# RFID_Reader.net
KiCad netlist of a schematic drawn in Altium Designer
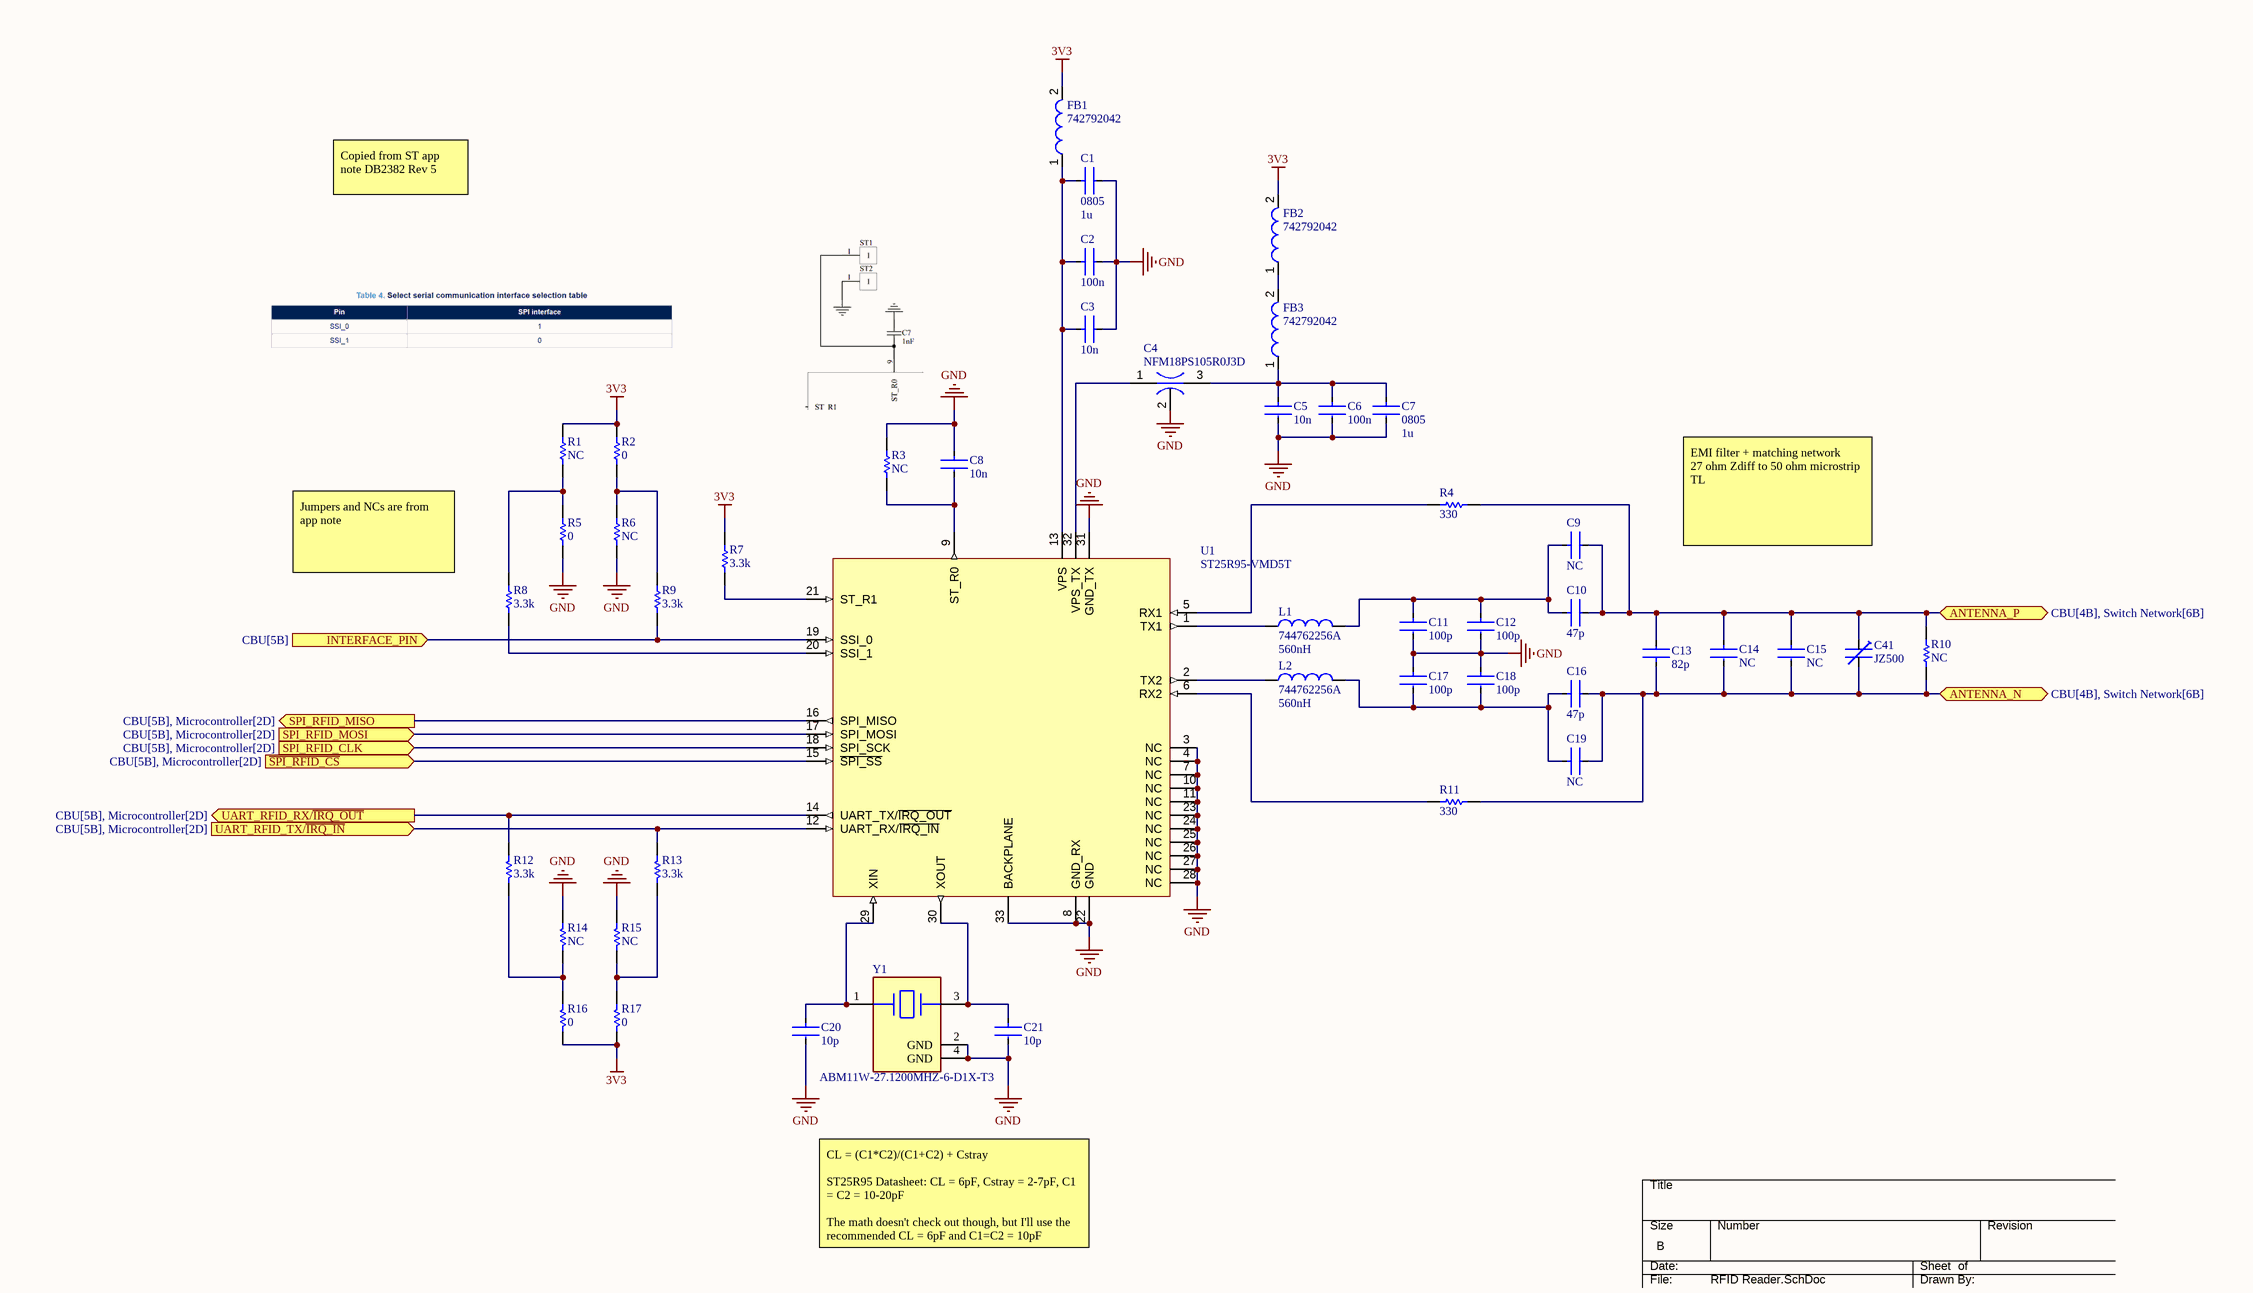
[diagram p0: RFID Reader.SchDoc]

(export (version "E")
  (design (tool "Eeschema 10.0.6"))
  (components
    (comp (ref "C1")
      (value "1u")
      (footprint "FP-0805-Capacitor-CL21-IPC_B")
      (description "CAP CER 50V X7R 0805")
      (fields
        (field (name "TOLERANCE") "0.1")
        (field (name "MANUFACTURER") "KEMET")
        (field (name "PACKAGE") "0805")
      )
      (libsource (lib "CBU-PCB") (part "Ceramic Capacitor 0805"))
    )
    (comp (ref "C2")
      (value "100n")
      (footprint "FP-0603-Capacitor-CL10-IPC_B")
      (description "CAP CER 50V X7R 0603")
      (fields (field (name "TOLERANCE") "0.1") (field (name "MANUFACTURER") "KEMET"))
      (libsource (lib "CBU-PCB") (part "Ceramic Capacitor 0603"))
    )
    (comp (ref "C3")
      (value "10n")
      (footprint "FP-0603-Capacitor-CL10-IPC_B")
      (description "CAP CER 50V X7R 0603")
      (fields (field (name "TOLERANCE") "0.1") (field (name "MANUFACTURER") "KEMET"))
      (libsource (lib "CBU-PCB") (part "Ceramic Capacitor 0603"))
    )
    (comp (ref "C4")
      (value "NFM18PS105R0J3D")
      (footprint "FP-NFM18-0_1-e0_05_0_35-MFG")
      (fields (field (name "VOLTAGE") "6.3V") (field (name "TOLERANCE") "20%"))
      (libsource (lib "CBU-PCB") (part "NFM18PS105R0J3D"))
    )
    (comp (ref "C5")
      (value "10n")
      (footprint "FP-0603-Capacitor-CL10-IPC_B")
      (description "CAP CER 50V X7R 0603")
      (fields (field (name "TOLERANCE") "0.1") (field (name "MANUFACTURER") "KEMET"))
      (libsource (lib "CBU-PCB") (part "Ceramic Capacitor 0603"))
    )
    (comp (ref "C6")
      (value "100n")
      (footprint "FP-0603-Capacitor-CL10-IPC_B")
      (description "CAP CER 50V X7R 0603")
      (fields (field (name "TOLERANCE") "0.1") (field (name "MANUFACTURER") "KEMET"))
      (libsource (lib "CBU-PCB") (part "Ceramic Capacitor 0603"))
    )
    (comp (ref "C7")
      (value "1u")
      (footprint "FP-0805-Capacitor-CL21-IPC_B")
      (description "CAP CER 50V X7R 0805")
      (fields
        (field (name "TOLERANCE") "0.1")
        (field (name "MANUFACTURER") "KEMET")
        (field (name "PACKAGE") "0805")
      )
      (libsource (lib "CBU-PCB") (part "Ceramic Capacitor 0805"))
    )
    (comp (ref "C8")
      (value "10n")
      (footprint "FP-0603-Capacitor-CL10-IPC_B")
      (description "CAP CER 50V X7R 0603")
      (fields (field (name "TOLERANCE") "0.1") (field (name "MANUFACTURER") "KEMET"))
      (libsource (lib "CBU-PCB") (part "Ceramic Capacitor 0603"))
    )
    (comp (ref "C9")
      (value "NC")
      (footprint "FP-0603-Capacitor-CL10-IPC_B")
      (description "CAP CER 50V X7R 0603")
      (fields (field (name "TOLERANCE") "0.1") (field (name "MANUFACTURER") "KEMET"))
      (libsource (lib "CBU-PCB") (part "Ceramic Capacitor 0603"))
    )
    (comp (ref "C10")
      (value "47p")
      (footprint "FP-0603-Capacitor-CL10-IPC_B")
      (description "CAP CER 50V X7R 0603")
      (fields (field (name "TOLERANCE") "0.1") (field (name "MANUFACTURER") "KEMET"))
      (libsource (lib "CBU-PCB") (part "Ceramic Capacitor 0603"))
    )
    (comp (ref "C11")
      (value "100p")
      (footprint "FP-0603-Capacitor-CL10-IPC_B")
      (description "CAP CER 50V X7R 0603")
      (fields (field (name "TOLERANCE") "0.1") (field (name "MANUFACTURER") "KEMET"))
      (libsource (lib "CBU-PCB") (part "Ceramic Capacitor 0603"))
    )
    (comp (ref "C12")
      (value "100p")
      (footprint "FP-0603-Capacitor-CL10-IPC_B")
      (description "CAP CER 50V X7R 0603")
      (fields (field (name "TOLERANCE") "0.1") (field (name "MANUFACTURER") "KEMET"))
      (libsource (lib "CBU-PCB") (part "Ceramic Capacitor 0603"))
    )
    (comp (ref "C13")
      (value "82p")
      (footprint "FP-0603-Capacitor-CL10-IPC_B")
      (description "CAP CER 50V X7R 0603")
      (fields (field (name "TOLERANCE") "0.1") (field (name "MANUFACTURER") "KEMET"))
      (libsource (lib "CBU-PCB") (part "Ceramic Capacitor 0603"))
    )
    (comp (ref "C14")
      (value "NC")
      (footprint "FP-0603-Capacitor-CL10-IPC_B")
      (description "CAP CER 50V X7R 0603")
      (fields (field (name "TOLERANCE") "0.1") (field (name "MANUFACTURER") "KEMET"))
      (libsource (lib "CBU-PCB") (part "Ceramic Capacitor 0603"))
    )
    (comp (ref "C15")
      (value "NC")
      (footprint "FP-0603-Capacitor-CL10-IPC_B")
      (description "CAP CER 50V X7R 0603")
      (fields (field (name "TOLERANCE") "0.1") (field (name "MANUFACTURER") "KEMET"))
      (libsource (lib "CBU-PCB") (part "Ceramic Capacitor 0603"))
    )
    (comp (ref "C16")
      (value "47p")
      (footprint "FP-0603-Capacitor-CL10-IPC_B")
      (description "CAP CER 50V X7R 0603")
      (fields (field (name "TOLERANCE") "0.1") (field (name "MANUFACTURER") "KEMET"))
      (libsource (lib "CBU-PCB") (part "Ceramic Capacitor 0603"))
    )
    (comp (ref "C17")
      (value "100p")
      (footprint "FP-0603-Capacitor-CL10-IPC_B")
      (description "CAP CER 50V X7R 0603")
      (fields (field (name "TOLERANCE") "0.1") (field (name "MANUFACTURER") "KEMET"))
      (libsource (lib "CBU-PCB") (part "Ceramic Capacitor 0603"))
    )
    (comp (ref "C18")
      (value "100p")
      (footprint "FP-0603-Capacitor-CL10-IPC_B")
      (description "CAP CER 50V X7R 0603")
      (fields (field (name "TOLERANCE") "0.1") (field (name "MANUFACTURER") "KEMET"))
      (libsource (lib "CBU-PCB") (part "Ceramic Capacitor 0603"))
    )
    (comp (ref "C19")
      (value "NC")
      (footprint "FP-0603-Capacitor-CL10-IPC_B")
      (description "CAP CER 50V X7R 0603")
      (fields (field (name "TOLERANCE") "0.1") (field (name "MANUFACTURER") "KEMET"))
      (libsource (lib "CBU-PCB") (part "Ceramic Capacitor 0603"))
    )
    (comp (ref "C20")
      (value "10p")
      (footprint "FP-0603-Capacitor-CL10-IPC_B")
      (description "CAP CER 50V X7R 0603")
      (fields (field (name "TOLERANCE") "0.1") (field (name "MANUFACTURER") "KEMET"))
      (libsource (lib "CBU-PCB") (part "Ceramic Capacitor 0603"))
    )
    (comp (ref "C21")
      (value "10p")
      (footprint "FP-0603-Capacitor-CL10-IPC_B")
      (description "CAP CER 50V X7R 0603")
      (fields (field (name "TOLERANCE") "0.1") (field (name "MANUFACTURER") "KEMET"))
      (libsource (lib "CBU-PCB") (part "Ceramic Capacitor 0603"))
    )
    (comp (ref "C41")
      (value "JZ500")
      (footprint "JZXXX_Trim_Capacitor")
      (description "8 ~ 50pF Trimmer Capacitor 125 V Top Surface Mount")
      (libsource (lib "CBU-PCB") (part "JZ500"))
    )
    (comp (ref "FB1")
      (value "742792042")
      (footprint "742792042")
      (description "SMD EMI Suppression Ferrite Bead WE-CBF, Z = 600 Ohm")
      (libsource (lib "CBU-PCB") (part "742792042"))
    )
    (comp (ref "FB2")
      (value "742792042")
      (footprint "742792042")
      (description "SMD EMI Suppression Ferrite Bead WE-CBF, Z = 600 Ohm")
      (libsource (lib "CBU-PCB") (part "742792042"))
    )
    (comp (ref "FB3")
      (value "742792042")
      (footprint "742792042")
      (description "SMD EMI Suppression Ferrite Bead WE-CBF, Z = 600 Ohm")
      (libsource (lib "CBU-PCB") (part "742792042"))
    )
    (comp (ref "L1")
      (value "744762256A")
      (footprint "744762256A")
      (description "744762256A General Purpose Inductor, 0.56uH, 5%, 1 Element, Ceramic-Core, SMD, 1008")
      (fields (field (name "TOLERANCE") "5%") (field (name "INDUCTANCE") "560nH"))
      (libsource (lib "CBU-PCB") (part "744762256A"))
    )
    (comp (ref "L2")
      (value "744762256A")
      (footprint "744762256A")
      (description "744762256A General Purpose Inductor, 0.56uH, 5%, 1 Element, Ceramic-Core, SMD, 1008")
      (fields (field (name "TOLERANCE") "5%") (field (name "INDUCTANCE") "560nH"))
      (libsource (lib "CBU-PCB") (part "744762256A"))
    )
    (comp (ref "R1")
      (value "NC")
      (footprint "RESC1608X55X25NL10T15")
      (fields
        (field (name "TOLERANCE") "1%")
        (field (name "MANUFACTURER") "Yageo")
        (field (name "Comment") "RC0603FR-072K2L")
      )
      (libsource (lib "CBU-PCB") (part "Resistor 0603"))
    )
    (comp (ref "R2")
      (value "0")
      (footprint "RESC1608X55X25NL10T15")
      (fields
        (field (name "TOLERANCE") "1%")
        (field (name "MANUFACTURER") "Yageo")
        (field (name "Comment") "RC0603FR-072K2L")
      )
      (libsource (lib "CBU-PCB") (part "Resistor 0603"))
    )
    (comp (ref "R3")
      (value "NC")
      (footprint "RESC1608X55X25NL10T15")
      (fields
        (field (name "TOLERANCE") "1%")
        (field (name "MANUFACTURER") "Yageo")
        (field (name "Comment") "RC0603FR-072K2L")
      )
      (libsource (lib "CBU-PCB") (part "Resistor 0603"))
    )
    (comp (ref "R4")
      (value "330")
      (footprint "RESC1608X55X25NL10T15")
      (fields
        (field (name "TOLERANCE") "1%")
        (field (name "MANUFACTURER") "Yageo")
        (field (name "Comment") "RC0603FR-072K2L")
      )
      (libsource (lib "CBU-PCB") (part "Resistor 0603"))
    )
    (comp (ref "R5")
      (value "0")
      (footprint "RESC1608X55X25NL10T15")
      (fields
        (field (name "TOLERANCE") "1%")
        (field (name "MANUFACTURER") "Yageo")
        (field (name "Comment") "RC0603FR-072K2L")
      )
      (libsource (lib "CBU-PCB") (part "Resistor 0603"))
    )
    (comp (ref "R6")
      (value "NC")
      (footprint "RESC1608X55X25NL10T15")
      (fields
        (field (name "TOLERANCE") "1%")
        (field (name "MANUFACTURER") "Yageo")
        (field (name "Comment") "RC0603FR-072K2L")
      )
      (libsource (lib "CBU-PCB") (part "Resistor 0603"))
    )
    (comp (ref "R7")
      (value "3.3k")
      (footprint "RESC1608X55X25NL10T15")
      (fields
        (field (name "TOLERANCE") "1%")
        (field (name "MANUFACTURER") "Yageo")
        (field (name "Comment") "RC0603FR-072K2L")
      )
      (libsource (lib "CBU-PCB") (part "Resistor 0603"))
    )
    (comp (ref "R8")
      (value "3.3k")
      (footprint "RESC1608X55X25NL10T15")
      (fields
        (field (name "TOLERANCE") "1%")
        (field (name "MANUFACTURER") "Yageo")
        (field (name "Comment") "RC0603FR-072K2L")
      )
      (libsource (lib "CBU-PCB") (part "Resistor 0603"))
    )
    (comp (ref "R9")
      (value "3.3k")
      (footprint "RESC1608X55X25NL10T15")
      (fields
        (field (name "TOLERANCE") "1%")
        (field (name "MANUFACTURER") "Yageo")
        (field (name "Comment") "RC0603FR-072K2L")
      )
      (libsource (lib "CBU-PCB") (part "Resistor 0603"))
    )
    (comp (ref "R10")
      (value "NC")
      (footprint "RESC1608X55X25NL10T15")
      (fields
        (field (name "TOLERANCE") "1%")
        (field (name "MANUFACTURER") "Yageo")
        (field (name "Comment") "RC0603FR-072K2L")
      )
      (libsource (lib "CBU-PCB") (part "Resistor 0603"))
    )
    (comp (ref "R11")
      (value "330")
      (footprint "RESC1608X55X25NL10T15")
      (fields
        (field (name "TOLERANCE") "1%")
        (field (name "MANUFACTURER") "Yageo")
        (field (name "Comment") "RC0603FR-072K2L")
      )
      (libsource (lib "CBU-PCB") (part "Resistor 0603"))
    )
    (comp (ref "R12")
      (value "3.3k")
      (footprint "RESC1608X55X25NL10T15")
      (fields
        (field (name "TOLERANCE") "1%")
        (field (name "MANUFACTURER") "Yageo")
        (field (name "Comment") "RC0603FR-072K2L")
      )
      (libsource (lib "CBU-PCB") (part "Resistor 0603"))
    )
    (comp (ref "R13")
      (value "3.3k")
      (footprint "RESC1608X55X25NL10T15")
      (fields
        (field (name "TOLERANCE") "1%")
        (field (name "MANUFACTURER") "Yageo")
        (field (name "Comment") "RC0603FR-072K2L")
      )
      (libsource (lib "CBU-PCB") (part "Resistor 0603"))
    )
    (comp (ref "R14")
      (value "NC")
      (footprint "RESC1608X55X25NL10T15")
      (fields
        (field (name "TOLERANCE") "1%")
        (field (name "MANUFACTURER") "Yageo")
        (field (name "Comment") "RC0603FR-072K2L")
      )
      (libsource (lib "CBU-PCB") (part "Resistor 0603"))
    )
    (comp (ref "R15")
      (value "NC")
      (footprint "RESC1608X55X25NL10T15")
      (fields
        (field (name "TOLERANCE") "1%")
        (field (name "MANUFACTURER") "Yageo")
        (field (name "Comment") "RC0603FR-072K2L")
      )
      (libsource (lib "CBU-PCB") (part "Resistor 0603"))
    )
    (comp (ref "R16")
      (value "0")
      (footprint "RESC1608X55X25NL10T15")
      (fields
        (field (name "TOLERANCE") "1%")
        (field (name "MANUFACTURER") "Yageo")
        (field (name "Comment") "RC0603FR-072K2L")
      )
      (libsource (lib "CBU-PCB") (part "Resistor 0603"))
    )
    (comp (ref "R17")
      (value "0")
      (footprint "RESC1608X55X25NL10T15")
      (fields
        (field (name "TOLERANCE") "1%")
        (field (name "MANUFACTURER") "Yageo")
        (field (name "Comment") "RC0603FR-072K2L")
      )
      (libsource (lib "CBU-PCB") (part "Resistor 0603"))
    )
    (comp (ref "U1")
      (value "ST25R95-VMD5T")
      (footprint "ST25R95-VMD5T")
      (libsource (lib "CBU-PCB") (part "ST25R95-VMD5T"))
    )
    (comp (ref "Y1")
      (value "ABM11W-27.1200MHZ-6-D1X-T3")
      (footprint "FP-ABM11W-MFG")
      (description "Crystal 27.12MHz ±10ppm 6pF SMD-4 2mm x 1.6mm")
      (libsource (lib "CBU-PCB") (part "ABM11W-27.1200MHZ-6-D1X-T3"))
    )
  )
  (nets
    (net (code "1") (name "/ANTENNA_N") (class "Default")
      (node (ref "C13") (pin "1") (pinfunction "1_1") (pintype "passive"))
      (node (ref "C14") (pin "2") (pinfunction "2_2") (pintype "passive"))
      (node (ref "C15") (pin "2") (pinfunction "2_2") (pintype "passive"))
      (node (ref "C16") (pin "2") (pinfunction "2_2") (pintype "passive"))
      (node (ref "C19") (pin "2") (pinfunction "2_2") (pintype "passive"))
      (node (ref "C41") (pin "2") (pintype "passive"))
      (node (ref "R10") (pin "1") (pinfunction "1_1") (pintype "passive"))
      (node (ref "R11") (pin "1") (pinfunction "1_1") (pintype "passive"))
    )
    (net (code "2") (name "/ANTENNA_P") (class "Default")
      (node (ref "C10") (pin "2") (pinfunction "2_2") (pintype "passive"))
      (node (ref "C13") (pin "2") (pinfunction "2_2") (pintype "passive"))
      (node (ref "C14") (pin "1") (pinfunction "1_1") (pintype "passive"))
      (node (ref "C15") (pin "1") (pinfunction "1_1") (pintype "passive"))
      (node (ref "C41") (pin "1") (pintype "passive"))
      (node (ref "C9") (pin "2") (pinfunction "2_2") (pintype "passive"))
      (node (ref "R10") (pin "2") (pinfunction "2_2") (pintype "passive"))
      (node (ref "R4") (pin "1") (pinfunction "1_1") (pintype "passive"))
    )
    (net (code "3") (name "/INTERFACE_PIN") (class "Default")
      (node (ref "R9") (pin "1") (pinfunction "1_1") (pintype "passive"))
      (node (ref "U1") (pin "19") (pinfunction "SSI_0_19") (pintype "input"))
    )
    (net (code "4") (name "/SPI_RFID_CLK") (class "Default")
      (node (ref "U1") (pin "18") (pinfunction "SPI_SCK_18") (pintype "input"))
    )
    (net (code "5") (name "/SPI_RFID_MISO") (class "Default")
      (node (ref "U1") (pin "16") (pinfunction "SPI_MISO_16") (pintype "output"))
    )
    (net (code "6") (name "/SPI_RFID_MOSI") (class "Default")
      (node (ref "U1") (pin "17") (pinfunction "SPI_MOSI_17") (pintype "input"))
    )
    (net (code "7") (name "/UART_RFID_RX{slash}~{IRQ_OUT}") (class "Default")
      (node (ref "R12") (pin "1") (pinfunction "1_1") (pintype "passive"))
      (node (ref "U1") (pin "14") (pinfunction "UART_TX/~{IRQ_OUT}_14") (pintype "output"))
    )
    (net (code "8") (name "/UART_RFID_TX{slash}~{IRQ_IN}") (class "Default")
      (node (ref "R13") (pin "1") (pinfunction "1_1") (pintype "passive"))
      (node (ref "U1") (pin "12") (pinfunction "UART_RX/~{IRQ_IN}_12") (pintype "input"))
    )
    (net (code "9") (name "/~{SPI_RFID_CS}") (class "Default")
      (node (ref "U1") (pin "15") (pinfunction "~{SPI_SS}_15") (pintype "input"))
    )
    (net (code "10") (name "3V3") (class "Default")
      (node (ref "FB1") (pin "2") (pinfunction "2_2") (pintype "passive"))
      (node (ref "FB2") (pin "2") (pinfunction "2_2") (pintype "passive"))
      (node (ref "R1") (pin "2") (pinfunction "2_2") (pintype "passive"))
      (node (ref "R16") (pin "2") (pinfunction "2_2") (pintype "passive"))
      (node (ref "R17") (pin "2") (pinfunction "2_2") (pintype "passive"))
      (node (ref "R2") (pin "2") (pinfunction "2_2") (pintype "passive"))
      (node (ref "R7") (pin "2") (pinfunction "2_2") (pintype "passive"))
    )
    (net (code "11") (name "GND") (class "Default")
      (node (ref "C1") (pin "2") (pinfunction "2_2") (pintype "passive"))
      (node (ref "C11") (pin "2") (pinfunction "2_2") (pintype "passive"))
      (node (ref "C12") (pin "2") (pinfunction "2_2") (pintype "passive"))
      (node (ref "C17") (pin "1") (pinfunction "1_1") (pintype "passive"))
      (node (ref "C18") (pin "1") (pinfunction "1_1") (pintype "passive"))
      (node (ref "C2") (pin "2") (pinfunction "2_2") (pintype "passive"))
      (node (ref "C20") (pin "2") (pinfunction "2_2") (pintype "passive"))
      (node (ref "C21") (pin "2") (pinfunction "2_2") (pintype "passive"))
      (node (ref "C3") (pin "2") (pinfunction "2_2") (pintype "passive"))
      (node (ref "C4") (pin "2") (pinfunction "GND_2") (pintype "passive"))
      (node (ref "C5") (pin "2") (pinfunction "2_2") (pintype "passive"))
      (node (ref "C6") (pin "2") (pinfunction "2_2") (pintype "passive"))
      (node (ref "C7") (pin "2") (pinfunction "2_2") (pintype "passive"))
      (node (ref "C8") (pin "1") (pinfunction "1_1") (pintype "passive"))
      (node (ref "R14") (pin "1") (pinfunction "1_1") (pintype "passive"))
      (node (ref "R15") (pin "1") (pinfunction "1_1") (pintype "passive"))
      (node (ref "R3") (pin "1") (pinfunction "1_1") (pintype "passive"))
      (node (ref "R5") (pin "1") (pinfunction "1_1") (pintype "passive"))
      (node (ref "R6") (pin "1") (pinfunction "1_1") (pintype "passive"))
      (node (ref "U1") (pin "10") (pinfunction "NC_10") (pintype "passive"))
      (node (ref "U1") (pin "11") (pinfunction "NC_11") (pintype "passive"))
      (node (ref "U1") (pin "22") (pinfunction "GND_22") (pintype "power_in"))
      (node (ref "U1") (pin "23") (pinfunction "NC_23") (pintype "passive"))
      (node (ref "U1") (pin "24") (pinfunction "NC_24") (pintype "passive"))
      (node (ref "U1") (pin "25") (pinfunction "NC_25") (pintype "passive"))
      (node (ref "U1") (pin "26") (pinfunction "NC_26") (pintype "passive"))
      (node (ref "U1") (pin "27") (pinfunction "NC_27") (pintype "passive"))
      (node (ref "U1") (pin "28") (pinfunction "NC_28") (pintype "passive"))
      (node (ref "U1") (pin "3") (pinfunction "NC_3") (pintype "passive"))
      (node (ref "U1") (pin "31") (pinfunction "GND_TX_31") (pintype "power_in"))
      (node (ref "U1") (pin "33") (pinfunction "BACKPLANE_33") (pintype "passive"))
      (node (ref "U1") (pin "4") (pinfunction "NC_4") (pintype "passive"))
      (node (ref "U1") (pin "7") (pinfunction "NC_7") (pintype "passive"))
      (node (ref "U1") (pin "8") (pinfunction "GND_RX_8") (pintype "power_in"))
      (node (ref "Y1") (pin "2") (pinfunction "GND_2") (pintype "power_in"))
      (node (ref "Y1") (pin "4") (pinfunction "GND_4") (pintype "power_in"))
    )
    (net (code "12") (name "Net-(C4-Input)") (class "Default")
      (node (ref "C4") (pin "1") (pinfunction "Input_1") (pintype "passive"))
      (node (ref "U1") (pin "32") (pinfunction "VPS_TX_32") (pintype "power_in"))
    )
    (net (code "13") (name "Net-(C4-Output)") (class "Default")
      (node (ref "C4") (pin "3") (pinfunction "Output_3") (pintype "passive"))
      (node (ref "C5") (pin "1") (pinfunction "1_1") (pintype "passive"))
      (node (ref "C6") (pin "1") (pinfunction "1_1") (pintype "passive"))
      (node (ref "C7") (pin "1") (pinfunction "1_1") (pintype "passive"))
      (node (ref "FB3") (pin "1") (pinfunction "1_1") (pintype "passive"))
    )
    (net (code "14") (name "Net-(C10-Pad1)") (class "Default")
      (node (ref "C10") (pin "1") (pinfunction "1_1") (pintype "passive"))
      (node (ref "C11") (pin "1") (pinfunction "1_1") (pintype "passive"))
      (node (ref "C12") (pin "1") (pinfunction "1_1") (pintype "passive"))
      (node (ref "C9") (pin "1") (pinfunction "1_1") (pintype "passive"))
      (node (ref "L1") (pin "2") (pinfunction "2_2") (pintype "passive"))
    )
    (net (code "15") (name "Net-(C16-Pad1)") (class "Default")
      (node (ref "C16") (pin "1") (pinfunction "1_1") (pintype "passive"))
      (node (ref "C17") (pin "2") (pinfunction "2_2") (pintype "passive"))
      (node (ref "C18") (pin "2") (pinfunction "2_2") (pintype "passive"))
      (node (ref "C19") (pin "1") (pinfunction "1_1") (pintype "passive"))
      (node (ref "L2") (pin "2") (pinfunction "2_2") (pintype "passive"))
    )
    (net (code "16") (name "Net-(FB2-Pad1)") (class "Default")
      (node (ref "FB2") (pin "1") (pinfunction "1_1") (pintype "passive"))
      (node (ref "FB3") (pin "2") (pinfunction "2_2") (pintype "passive"))
    )
    (net (code "17") (name "Net-(R1-Pad1)") (class "Default")
      (node (ref "R1") (pin "1") (pinfunction "1_1") (pintype "passive"))
      (node (ref "R5") (pin "2") (pinfunction "2_2") (pintype "passive"))
      (node (ref "R8") (pin "2") (pinfunction "2_2") (pintype "passive"))
    )
    (net (code "18") (name "Net-(R2-Pad1)") (class "Default")
      (node (ref "R2") (pin "1") (pinfunction "1_1") (pintype "passive"))
      (node (ref "R6") (pin "2") (pinfunction "2_2") (pintype "passive"))
      (node (ref "R9") (pin "2") (pinfunction "2_2") (pintype "passive"))
    )
    (net (code "19") (name "Net-(R12-Pad2)") (class "Default")
      (node (ref "R12") (pin "2") (pinfunction "2_2") (pintype "passive"))
      (node (ref "R14") (pin "2") (pinfunction "2_2") (pintype "passive"))
      (node (ref "R16") (pin "1") (pinfunction "1_1") (pintype "passive"))
    )
    (net (code "20") (name "Net-(R13-Pad2)") (class "Default")
      (node (ref "R13") (pin "2") (pinfunction "2_2") (pintype "passive"))
      (node (ref "R15") (pin "2") (pinfunction "2_2") (pintype "passive"))
      (node (ref "R17") (pin "1") (pinfunction "1_1") (pintype "passive"))
    )
    (net (code "21") (name "Net-(U1-RX1)") (class "Default")
      (node (ref "R4") (pin "2") (pinfunction "2_2") (pintype "passive"))
      (node (ref "U1") (pin "5") (pinfunction "RX1_5") (pintype "input"))
    )
    (net (code "22") (name "Net-(U1-RX2)") (class "Default")
      (node (ref "R11") (pin "2") (pinfunction "2_2") (pintype "passive"))
      (node (ref "U1") (pin "6") (pinfunction "RX2_6") (pintype "input"))
    )
    (net (code "23") (name "Net-(U1-SSI_1)") (class "Default")
      (node (ref "R8") (pin "1") (pinfunction "1_1") (pintype "passive"))
      (node (ref "U1") (pin "20") (pinfunction "SSI_1_20") (pintype "input"))
    )
    (net (code "24") (name "Net-(U1-ST_R0)") (class "Default")
      (node (ref "C8") (pin "2") (pinfunction "2_2") (pintype "passive"))
      (node (ref "R3") (pin "2") (pinfunction "2_2") (pintype "passive"))
      (node (ref "U1") (pin "9") (pinfunction "ST_R0_9") (pintype "output"))
    )
    (net (code "25") (name "Net-(U1-ST_R1)") (class "Default")
      (node (ref "R7") (pin "1") (pinfunction "1_1") (pintype "passive"))
      (node (ref "U1") (pin "21") (pinfunction "ST_R1_21") (pintype "input"))
    )
    (net (code "26") (name "Net-(U1-TX1)") (class "Default")
      (node (ref "L1") (pin "1") (pinfunction "1_1") (pintype "passive"))
      (node (ref "U1") (pin "1") (pinfunction "TX1_1") (pintype "output"))
    )
    (net (code "27") (name "Net-(U1-TX2)") (class "Default")
      (node (ref "L2") (pin "1") (pinfunction "1_1") (pintype "passive"))
      (node (ref "U1") (pin "2") (pinfunction "TX2_2") (pintype "output"))
    )
    (net (code "28") (name "Net-(U1-VPS)") (class "Default")
      (node (ref "C1") (pin "1") (pinfunction "1_1") (pintype "passive"))
      (node (ref "C2") (pin "1") (pinfunction "1_1") (pintype "passive"))
      (node (ref "C3") (pin "1") (pinfunction "1_1") (pintype "passive"))
      (node (ref "FB1") (pin "1") (pinfunction "1_1") (pintype "passive"))
      (node (ref "U1") (pin "13") (pinfunction "VPS_13") (pintype "power_in"))
    )
    (net (code "29") (name "Net-(U1-XIN)") (class "Default")
      (node (ref "C20") (pin "1") (pinfunction "1_1") (pintype "passive"))
      (node (ref "U1") (pin "29") (pinfunction "XIN_29") (pintype "input"))
      (node (ref "Y1") (pin "1") (pinfunction "1_1") (pintype "passive"))
    )
    (net (code "30") (name "Net-(U1-XOUT)") (class "Default")
      (node (ref "C21") (pin "1") (pinfunction "1_1") (pintype "passive"))
      (node (ref "U1") (pin "30") (pinfunction "XOUT_30") (pintype "output"))
      (node (ref "Y1") (pin "3") (pinfunction "3_3") (pintype "passive"))
    )
  )
)
